# Andromeda-UIXO.net
KiCad netlist of a schematic drawn in Altium Designer
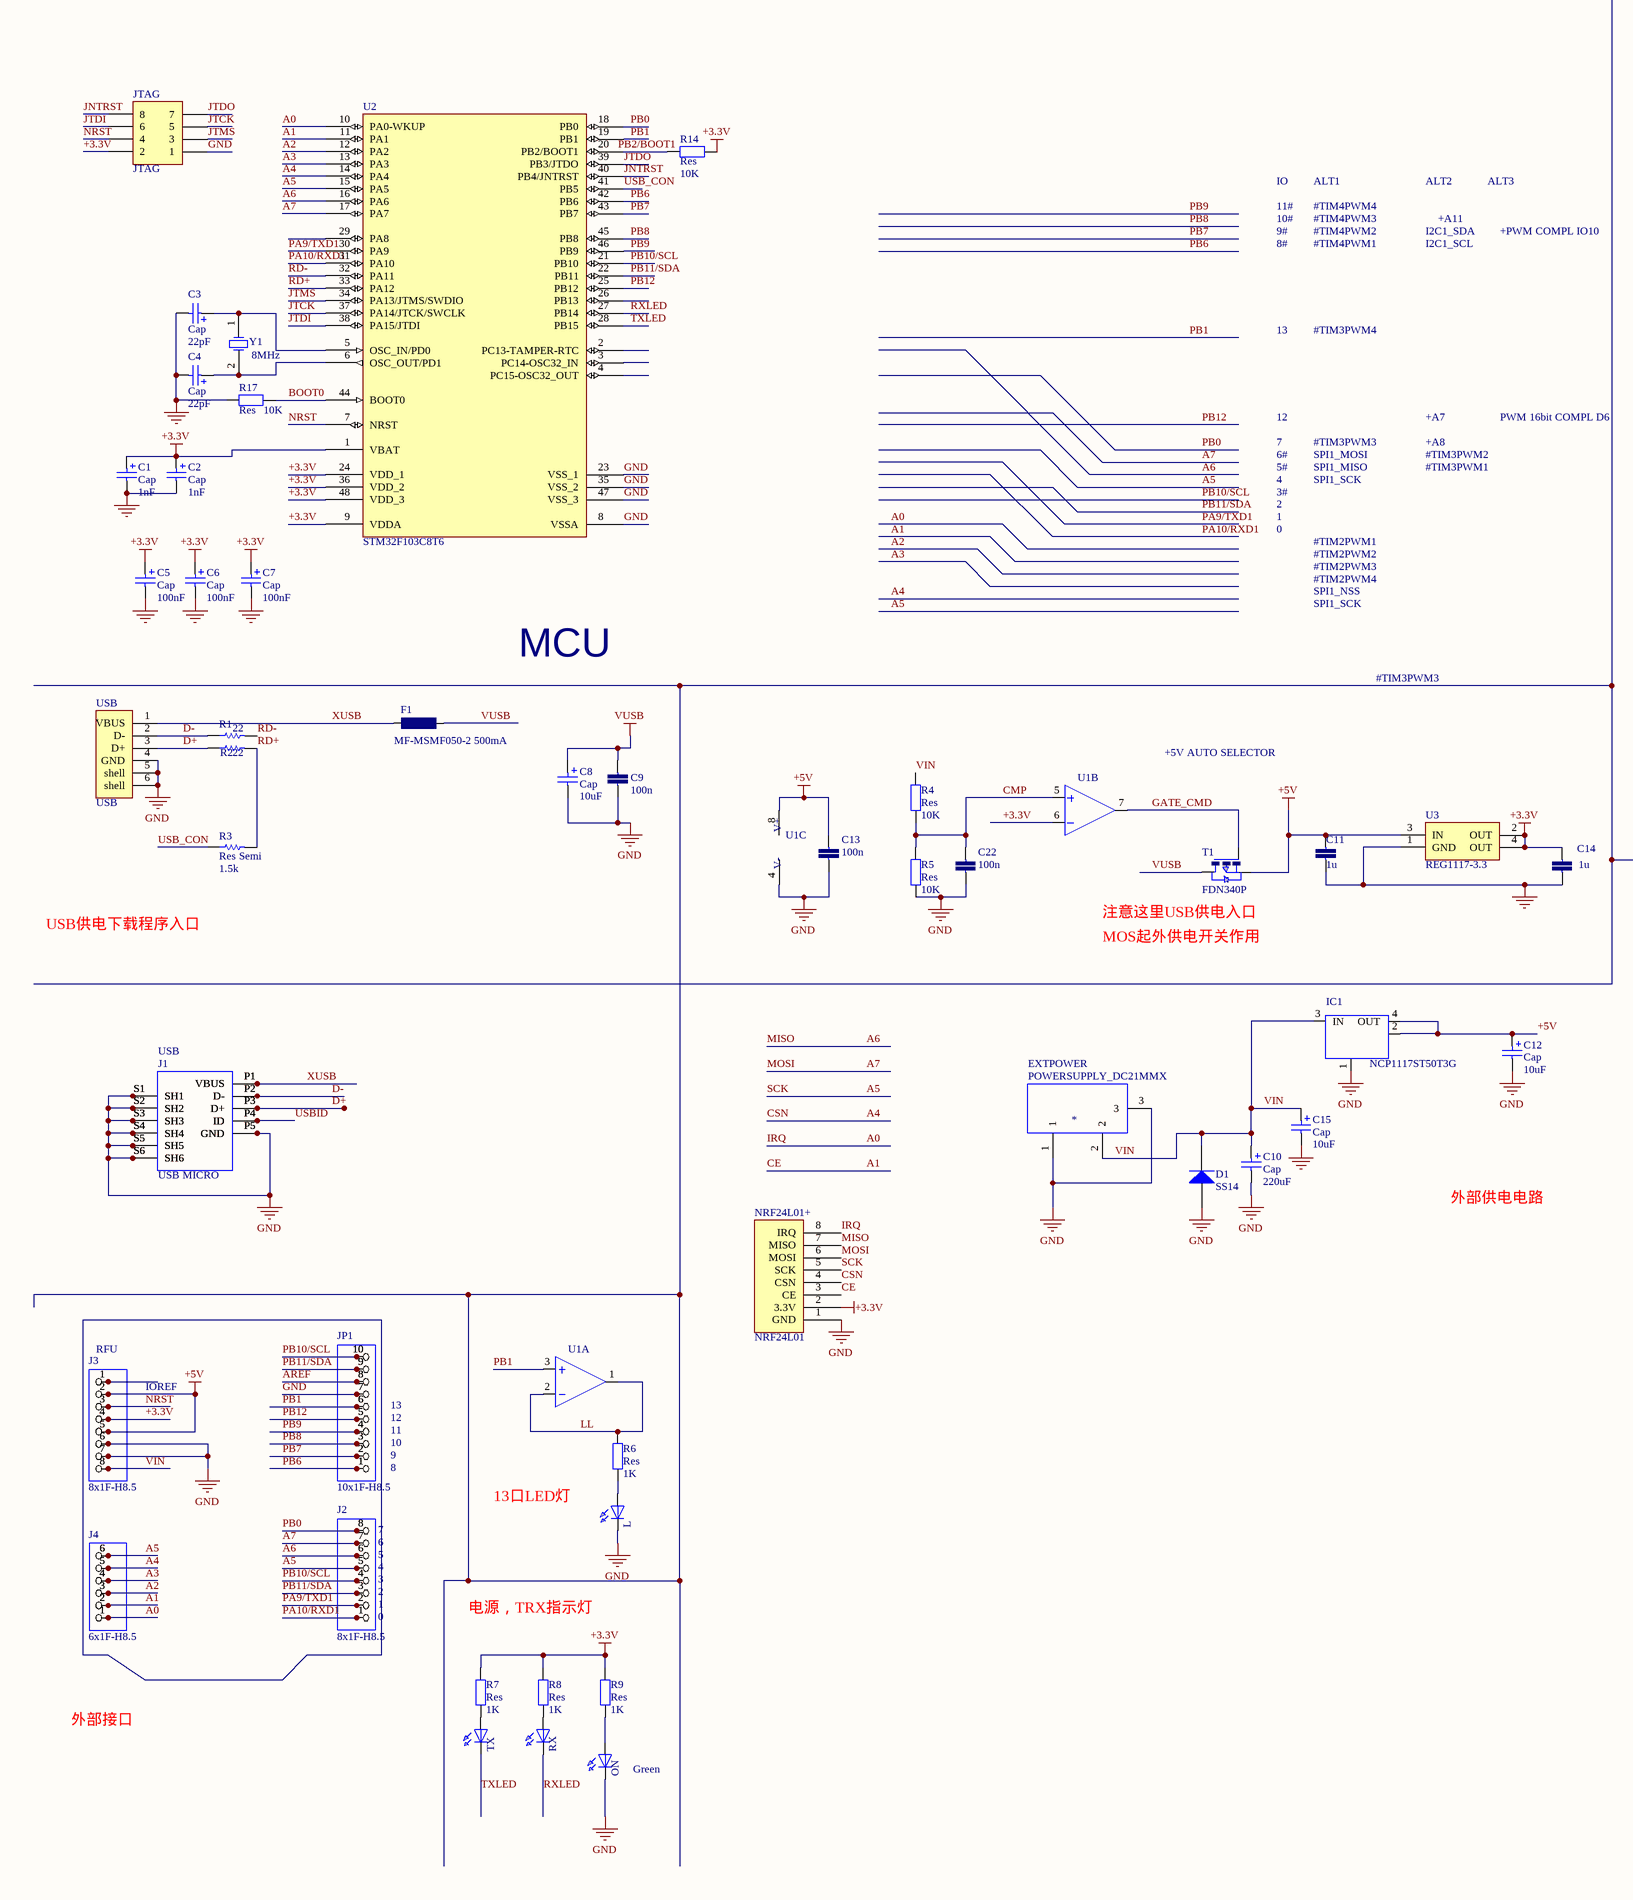
[diagram p0: Andromeda-UIXO.SchDoc, left]

(export (version "E")
  (design (tool "Eeschema 10.0.6"))
  (components
    (comp (ref "C1")
      (value "Cap")
      (footprint "RES0805(2012M)")
      (fields (field (name "ALTIUM_VALUE") "1nF"))
      (libsource (lib "*") (part "Cap"))
    )
    (comp (ref "C2")
      (value "Cap")
      (footprint "RES0805(2012M)")
      (fields (field (name "ALTIUM_VALUE") "1nF"))
      (libsource (lib "*") (part "Cap"))
    )
    (comp (ref "C3")
      (value "Cap")
      (footprint "RES0805(2012M)")
      (fields (field (name "ALTIUM_VALUE") "22pF"))
      (libsource (lib "*") (part "Cap"))
    )
    (comp (ref "C4")
      (value "Cap")
      (footprint "RES0805(2012M)")
      (fields (field (name "ALTIUM_VALUE") "22pF"))
      (libsource (lib "*") (part "Cap"))
    )
    (comp (ref "C5")
      (value "Cap")
      (footprint "RES0805(2012M)")
      (fields (field (name "ALTIUM_VALUE") "100nF"))
      (libsource (lib "*") (part "Cap"))
    )
    (comp (ref "C6")
      (value "Cap")
      (footprint "RES0805(2012M)")
      (fields (field (name "ALTIUM_VALUE") "100nF"))
      (libsource (lib "*") (part "Cap"))
    )
    (comp (ref "C7")
      (value "Cap")
      (footprint "RES0805(2012M)")
      (fields (field (name "ALTIUM_VALUE") "100nF"))
      (libsource (lib "*") (part "Cap"))
    )
    (comp (ref "C8")
      (value "Cap")
      (footprint "RES0805(2012M)")
      (fields (field (name "ALTIUM_VALUE") "10uF"))
      (libsource (lib "*") (part "Cap"))
    )
    (comp (ref "C9")
      (value "100n")
      (footprint "RES0805(2012M)")
      (libsource (lib "SmartPrj") (part "C-EUC0603"))
    )
    (comp (ref "C10")
      (value "Cap")
      (footprint "CAP_SMD")
      (fields (field (name "ALTIUM_VALUE") "220uF"))
      (libsource (lib "*") (part "Cap"))
    )
    (comp (ref "C11")
      (value "1u")
      (footprint "RES0805(2012M)")
      (libsource (lib "SmartPrj") (part "C-EUC0603"))
    )
    (comp (ref "C12")
      (value "Cap")
      (footprint "RES0805(2012M)")
      (fields (field (name "ALTIUM_VALUE") "10uF"))
      (libsource (lib "*") (part "Cap"))
    )
    (comp (ref "C13") (value "100n") (footprint "RES0805(2012M)") (libsource (lib "") (part "C-EUC0603_1")))
    (comp (ref "C14") (value "1u") (footprint "RES0805(2012M)") (libsource (lib "") (part "C-EUC0603_2")))
    (comp (ref "C15")
      (value "Cap")
      (footprint "RES0805(2012M)")
      (fields (field (name "ALTIUM_VALUE") "10uF"))
      (libsource (lib "*") (part "Cap"))
    )
    (comp (ref "C22")
      (value "100n")
      (footprint "RES0805(2012M)")
      (libsource (lib "SmartPrj") (part "C-EUC0603"))
    )
    (comp (ref "D1") (value "SS14") (footprint "DIODE_SMA") (libsource (lib "*") (part "DIODE_SWITCH")))
    (comp (ref "EXTPOWER")
      (value "*")
      (footprint "POWERSUPPLY_DC-21MM")
      (libsource (lib "SmartPrj") (part "POWERSUPPLY_DC21MMX"))
    )
    (comp (ref "F1")
      (value "MF-MSMF050-2 500mA")
      (footprint "L1812")
      (libsource (lib "rcl") (part "L-EUL1812"))
    )
    (comp (ref "IC1")
      (value "NCP1117ST50T3G")
      (footprint "SOT223")
      (libsource (lib "linear") (part "MC33269ST-3.3T3"))
    )
    (comp (ref "J1")
      (value "USB MICRO")
      (footprint "CON2_USB_MICRO_B_AT")
      (libsource (lib "SmartPrj") (part "MYCON2_USB-MINI-B"))
    )
    (comp (ref "J2") (value "8x1F-H8.5") (footprint "1X08") (libsource (lib "SmartPrj") (part "PINHD-1X8")))
    (comp (ref "J3") (value "8x1F-H8.5") (footprint "1X08") (libsource (lib "SmartPrj") (part "PINHD-1X8")))
    (comp (ref "J4") (value "6x1F-H8.5") (footprint "1X06") (libsource (lib "SmartPrj") (part "PINHD-1X6")))
    (comp (ref "JP1")
      (value "10x1F-H8.5")
      (footprint "1X10")
      (libsource (lib "SmartPrj") (part "PINHD-1X10"))
    )
    (comp (ref "JTAG")
      (value "JTAG")
      (footprint "HDR2X4")
      (description "Header, 4-Pin, Dual row")
      (fields (field (name "PUBLISHER") "Altium Limited"))
      (libsource (lib "*") (part "Header 4X2"))
    )
    (comp (ref "L")
      (value "Yellow")
      (footprint "CHIPLED_0805")
      (libsource (lib "led") (part "LEDCHIPLED_0805"))
    )
    (comp (ref "NRF24L01+")
      (value "NRF24L01")
      (footprint "NRF24L01")
      (description "NRF24L01+")
      (libsource (lib "NRF24L01") (part "NRF24L01"))
    )
    (comp (ref "ON")
      (value "Green")
      (footprint "CHIPLED_0805")
      (libsource (lib "led") (part "LEDCHIPLED_0805"))
    )
    (comp (ref "R1")
      (value "22")
      (footprint "RES0805(2012M)")
      (description "Semiconductor Resistor")
      (fields (field (name "Comment") "Res Semi") (field (name "PUBLISHER") "Altium Limited"))
      (libsource (lib "Miscellaneous Devices") (part "Res Semi"))
    )
    (comp (ref "R2")
      (value "22")
      (footprint "RES0805(2012M)")
      (description "Semiconductor Resistor")
      (fields (field (name "Comment") "Res Semi") (field (name "PUBLISHER") "Altium Limited"))
      (libsource (lib "Miscellaneous Devices") (part "Res Semi"))
    )
    (comp (ref "R3")
      (value "Res Semi")
      (footprint "RES0805(2012M)")
      (description "Semiconductor Resistor")
      (fields (field (name "ALTIUM_VALUE") "1.5k") (field (name "PUBLISHER") "Altium Limited"))
      (libsource (lib "Miscellaneous Devices") (part "Res Semi"))
    )
    (comp (ref "R4")
      (value "Res")
      (footprint "RES0805(2012M)")
      (description "Resistor")
      (fields (field (name "ALTIUM_VALUE") "10K"))
      (libsource (lib "") (part "Res_1"))
    )
    (comp (ref "R5")
      (value "Res")
      (footprint "RES0805(2012M)")
      (description "Resistor")
      (fields (field (name "ALTIUM_VALUE") "10K"))
      (libsource (lib "") (part "Res_1"))
    )
    (comp (ref "R6")
      (value "Res")
      (footprint "RES0805(2012M)")
      (description "Resistor")
      (fields (field (name "ALTIUM_VALUE") "1K"))
      (libsource (lib "") (part "Res_1"))
    )
    (comp (ref "R7")
      (value "Res")
      (footprint "RES0805(2012M)")
      (description "Resistor")
      (fields (field (name "ALTIUM_VALUE") "1K"))
      (libsource (lib "") (part "Res_1"))
    )
    (comp (ref "R8")
      (value "Res")
      (footprint "RES0805(2012M)")
      (description "Resistor")
      (fields (field (name "ALTIUM_VALUE") "1K"))
      (libsource (lib "") (part "Res_1"))
    )
    (comp (ref "R9")
      (value "Res")
      (footprint "RES0805(2012M)")
      (description "Resistor")
      (fields (field (name "ALTIUM_VALUE") "1K"))
      (libsource (lib "") (part "Res_1"))
    )
    (comp (ref "R14")
      (value "Res")
      (footprint "RES0805(2012M)")
      (description "Resistor")
      (fields (field (name "ALTIUM_VALUE") "10K"))
      (libsource (lib "*") (part "Res"))
    )
    (comp (ref "R17")
      (value "Res")
      (footprint "RES0805(2012M)")
      (description "Resistor")
      (fields (field (name "ALTIUM_VALUE") "10K"))
      (libsource (lib "*") (part "Res"))
    )
    (comp (ref "RX")
      (value "Yellow")
      (footprint "CHIPLED_0805")
      (libsource (lib "led") (part "LEDCHIPLED_0805"))
    )
    (comp (ref "T1") (value "FDN340P") (footprint "SOT-23") (libsource (lib "zetex") (part "PMOSSOT23")))
    (comp (ref "TX")
      (value "Yellow")
      (footprint "CHIPLED_0805")
      (libsource (lib "led") (part "LEDCHIPLED_0805"))
    )
    (comp (ref "U1")
      (value "LMV358IDGKR")
      (footprint "SO-8 LM358")
      (libsource (lib "Andromeda-UIXO") (part "LMV358MMX"))
    )
    (comp (ref "U2")
      (value "STM32F103C8T6")
      (footprint "LQFP48_M")
      (description "STM32 ARM-based 32-bit MCU with 64 Kbytes Flash, 48-pin LQFP, Industrial Temperature")
      (fields (field (name "PUBLISHER") "Altium Limited"))
      (libsource (lib "*") (part "STM32F103C8T6"))
    )
    (comp (ref "U3")
      (value "REG1117-3.3")
      (footprint "SOT223")
      (description "800mA and 1A Low Dropout Positive Regulator 2.85V, 3.3V, 5V, and Adjustable")
      (fields (field (name "PUBLISHER") "Altium Limited"))
      (libsource (lib "*") (part "REG1117-3.3"))
    )
    (comp (ref "USB") (value "USB") (footprint "USB/SM2.5-4H4A") (libsource (lib "*") (part "USB")))
    (comp (ref "Y1")
      (value "8MHz")
      (footprint "XTAL_0.4")
      (description "Crystal Oscillator")
      (fields (field (name "PUBLISHER") "Altium Limited"))
      (libsource (lib "*") (part "XTAL"))
    )
  )
  (nets
    (net (code "1") (name "+3.3V") (class "Default")
      (node (ref "C1") (pin "1") (pinfunction "1_1") (pintype "passive"))
      (node (ref "C14") (pin "2") (pinfunction "2_2") (pintype "passive"))
      (node (ref "C2") (pin "1") (pinfunction "1_1") (pintype "passive"))
      (node (ref "C5") (pin "1") (pinfunction "1_1") (pintype "passive"))
      (node (ref "C6") (pin "1") (pinfunction "1_1") (pintype "passive"))
      (node (ref "C7") (pin "1") (pinfunction "1_1") (pintype "passive"))
      (node (ref "J3") (pin "4") (pinfunction "4_4") (pintype "passive"))
      (node (ref "JTAG") (pin "2") (pinfunction "2_2") (pintype "passive"))
      (node (ref "NRF24L01+") (pin "2") (pinfunction "3.3V_2") (pintype "passive"))
      (node (ref "R14") (pin "1") (pinfunction "1_1") (pintype "passive"))
      (node (ref "R7") (pin "1") (pinfunction "1_1") (pintype "passive"))
      (node (ref "R8") (pin "1") (pinfunction "1_1") (pintype "passive"))
      (node (ref "R9") (pin "1") (pinfunction "1_1") (pintype "passive"))
      (node (ref "U1") (pin "6") (pinfunction "-IN_6") (pintype "passive"))
      (node (ref "U2") (pin "1") (pinfunction "VBAT_1") (pintype "power_in"))
      (node (ref "U2") (pin "24") (pinfunction "VDD_1_24") (pintype "power_in"))
      (node (ref "U2") (pin "36") (pinfunction "VDD_2_36") (pintype "power_in"))
      (node (ref "U2") (pin "48") (pinfunction "VDD_3_48") (pintype "power_in"))
      (node (ref "U2") (pin "9") (pinfunction "VDDA_9") (pintype "power_in"))
      (node (ref "U3") (pin "2") (pinfunction "OUT_2") (pintype "power_in"))
      (node (ref "U3") (pin "4") (pinfunction "OUT_4") (pintype "power_in"))
    )
    (net (code "2") (name "+5V") (class "Default")
      (node (ref "C11") (pin "2") (pinfunction "2_2") (pintype "passive"))
      (node (ref "C12") (pin "1") (pinfunction "1_1") (pintype "passive"))
      (node (ref "C13") (pin "1") (pinfunction "1_1") (pintype "passive"))
      (node (ref "IC1") (pin "2") (pinfunction "OUT@1_2") (pintype "passive"))
      (node (ref "IC1") (pin "4") (pinfunction "OUT_4") (pintype "passive"))
      (node (ref "J3") (pin "2") (pinfunction "2_2") (pintype "passive"))
      (node (ref "J3") (pin "5") (pinfunction "5_5") (pintype "passive"))
      (node (ref "T1") (pin "2") (pinfunction "S_2") (pintype "passive"))
      (node (ref "U1") (pin "8") (pinfunction "V+_8") (pintype "passive"))
      (node (ref "U3") (pin "3") (pinfunction "IN_3") (pintype "power_in"))
    )
    (net (code "3") (name "/A0") (class "Default")
      (node (ref "J4") (pin "1") (pinfunction "1_1") (pintype "passive"))
      (node (ref "NRF24L01+") (pin "8") (pinfunction "IRQ_8") (pintype "passive"))
      (node (ref "U2") (pin "10") (pinfunction "PA0-WKUP_10") (pintype "bidirectional"))
    )
    (net (code "4") (name "/A1") (class "Default")
      (node (ref "J4") (pin "2") (pinfunction "2_2") (pintype "passive"))
      (node (ref "NRF24L01+") (pin "3") (pinfunction "CE_3") (pintype "passive"))
      (node (ref "U2") (pin "11") (pinfunction "PA1_11") (pintype "bidirectional"))
    )
    (net (code "5") (name "/A2") (class "Default")
      (node (ref "J4") (pin "3") (pinfunction "3_3") (pintype "passive"))
      (node (ref "U2") (pin "12") (pinfunction "PA2_12") (pintype "bidirectional"))
    )
    (net (code "6") (name "/A3") (class "Default")
      (node (ref "J4") (pin "4") (pinfunction "4_4") (pintype "passive"))
      (node (ref "U2") (pin "13") (pinfunction "PA3_13") (pintype "bidirectional"))
    )
    (net (code "7") (name "/A4") (class "Default")
      (node (ref "J4") (pin "5") (pinfunction "5_5") (pintype "passive"))
      (node (ref "NRF24L01+") (pin "4") (pinfunction "CSN_4") (pintype "passive"))
      (node (ref "U2") (pin "14") (pinfunction "PA4_14") (pintype "bidirectional"))
    )
    (net (code "8") (name "/A5") (class "Default")
      (node (ref "J2") (pin "5") (pinfunction "5_5") (pintype "passive"))
      (node (ref "J4") (pin "6") (pinfunction "6_6") (pintype "passive"))
      (node (ref "NRF24L01+") (pin "5") (pinfunction "SCK_5") (pintype "passive"))
      (node (ref "U2") (pin "15") (pinfunction "PA5_15") (pintype "bidirectional"))
    )
    (net (code "9") (name "/A6") (class "Default")
      (node (ref "J2") (pin "6") (pinfunction "6_6") (pintype "passive"))
      (node (ref "NRF24L01+") (pin "7") (pinfunction "MISO_7") (pintype "passive"))
      (node (ref "U2") (pin "16") (pinfunction "PA6_16") (pintype "bidirectional"))
    )
    (net (code "10") (name "/A7") (class "Default")
      (node (ref "J2") (pin "7") (pinfunction "7_7") (pintype "passive"))
      (node (ref "NRF24L01+") (pin "6") (pinfunction "MOSI_6") (pintype "passive"))
      (node (ref "U2") (pin "17") (pinfunction "PA7_17") (pintype "bidirectional"))
    )
    (net (code "11") (name "/AREF") (class "Default")
      (node (ref "JP1") (pin "8") (pinfunction "8_8") (pintype "passive"))
    )
    (net (code "12") (name "/BOOT0") (class "Default")
      (node (ref "R17") (pin "1") (pinfunction "1_1") (pintype "passive"))
      (node (ref "U2") (pin "44") (pinfunction "BOOT0_44") (pintype "input"))
    )
    (net (code "13") (name "/CMP") (class "Default")
      (node (ref "C22") (pin "2") (pinfunction "2_2") (pintype "passive"))
      (node (ref "R4") (pin "2") (pinfunction "2_2") (pintype "passive"))
      (node (ref "R5") (pin "1") (pinfunction "1_1") (pintype "passive"))
      (node (ref "U1") (pin "5") (pinfunction "+IN_5") (pintype "passive"))
    )
    (net (code "14") (name "/D+") (class "Default")
      (node (ref "J1") (pin "P3") (pinfunction "D+_P3") (pintype "passive"))
      (node (ref "R2") (pin "1") (pinfunction "1_1") (pintype "passive"))
      (node (ref "USB") (pin "3") (pinfunction "D+_3") (pintype "passive"))
    )
    (net (code "15") (name "/D-") (class "Default")
      (node (ref "J1") (pin "P2") (pinfunction "D-_P2") (pintype "passive"))
      (node (ref "R1") (pin "1") (pinfunction "1_1") (pintype "passive"))
      (node (ref "USB") (pin "2") (pinfunction "D-_2") (pintype "passive"))
    )
    (net (code "16") (name "/GATE_CMD") (class "Default")
      (node (ref "T1") (pin "3") (pinfunction "G_3") (pintype "passive"))
      (node (ref "U1") (pin "7") (pinfunction "OUT_7") (pintype "passive"))
    )
    (net (code "17") (name "/JNTRST") (class "Default")
      (node (ref "JTAG") (pin "8") (pinfunction "8_8") (pintype "passive"))
      (node (ref "U2") (pin "40") (pinfunction "PB4/JNTRST_40") (pintype "bidirectional"))
    )
    (net (code "18") (name "/JTCK") (class "Default")
      (node (ref "JTAG") (pin "5") (pinfunction "5_5") (pintype "passive"))
      (node (ref "U2") (pin "37") (pinfunction "PA14/JTCK/SWCLK_37") (pintype "bidirectional"))
    )
    (net (code "19") (name "/JTDI") (class "Default")
      (node (ref "JTAG") (pin "6") (pinfunction "6_6") (pintype "passive"))
      (node (ref "U2") (pin "38") (pinfunction "PA15/JTDI_38") (pintype "bidirectional"))
    )
    (net (code "20") (name "/JTDO") (class "Default")
      (node (ref "JTAG") (pin "7") (pinfunction "7_7") (pintype "passive"))
      (node (ref "U2") (pin "39") (pinfunction "PB3/JTDO_39") (pintype "bidirectional"))
    )
    (net (code "21") (name "/JTMS") (class "Default")
      (node (ref "JTAG") (pin "3") (pinfunction "3_3") (pintype "passive"))
      (node (ref "U2") (pin "34") (pinfunction "PA13/JTMS/SWDIO_34") (pintype "bidirectional"))
    )
    (net (code "22") (name "/LL") (class "Default")
      (node (ref "R6") (pin "1") (pinfunction "1_1") (pintype "passive"))
      (node (ref "U1") (pin "1") (pinfunction "OUT_1") (pintype "passive"))
      (node (ref "U1") (pin "2") (pinfunction "-IN_2") (pintype "passive"))
    )
    (net (code "23") (name "/NRST") (class "Default")
      (node (ref "J3") (pin "3") (pinfunction "3_3") (pintype "passive"))
      (node (ref "JTAG") (pin "4") (pinfunction "4_4") (pintype "passive"))
      (node (ref "U2") (pin "7") (pinfunction "NRST_7") (pintype "bidirectional"))
    )
    (net (code "24") (name "/PA9{slash}TXD1") (class "Default")
      (node (ref "J2") (pin "2") (pinfunction "2_2") (pintype "passive"))
      (node (ref "U2") (pin "30") (pinfunction "PA9_30") (pintype "bidirectional"))
    )
    (net (code "25") (name "/PA10{slash}RXD1") (class "Default")
      (node (ref "J2") (pin "1") (pinfunction "1_1") (pintype "passive"))
      (node (ref "U2") (pin "31") (pinfunction "PA10_31") (pintype "bidirectional"))
    )
    (net (code "26") (name "/PB0") (class "Default")
      (node (ref "J2") (pin "8") (pinfunction "8_8") (pintype "passive"))
      (node (ref "U2") (pin "18") (pinfunction "PB0_18") (pintype "bidirectional"))
    )
    (net (code "27") (name "/PB1") (class "Default")
      (node (ref "JP1") (pin "6") (pinfunction "6_6") (pintype "passive"))
      (node (ref "U1") (pin "3") (pinfunction "+IN_3") (pintype "passive"))
      (node (ref "U2") (pin "19") (pinfunction "PB1_19") (pintype "bidirectional"))
    )
    (net (code "29") (name "/PB6") (class "Default")
      (node (ref "JP1") (pin "1") (pinfunction "1_1") (pintype "passive"))
      (node (ref "U2") (pin "42") (pinfunction "PB6_42") (pintype "bidirectional"))
    )
    (net (code "30") (name "/PB7") (class "Default")
      (node (ref "JP1") (pin "2") (pinfunction "2_2") (pintype "passive"))
      (node (ref "U2") (pin "43") (pinfunction "PB7_43") (pintype "bidirectional"))
    )
    (net (code "31") (name "/PB8") (class "Default")
      (node (ref "JP1") (pin "3") (pinfunction "3_3") (pintype "passive"))
      (node (ref "U2") (pin "45") (pinfunction "PB8_45") (pintype "bidirectional"))
    )
    (net (code "32") (name "/PB9") (class "Default")
      (node (ref "JP1") (pin "4") (pinfunction "4_4") (pintype "passive"))
      (node (ref "U2") (pin "46") (pinfunction "PB9_46") (pintype "bidirectional"))
    )
    (net (code "33") (name "/PB10{slash}SCL") (class "Default")
      (node (ref "J2") (pin "4") (pinfunction "4_4") (pintype "passive"))
      (node (ref "JP1") (pin "10") (pinfunction "10_10") (pintype "passive"))
      (node (ref "U2") (pin "21") (pinfunction "PB10_21") (pintype "bidirectional"))
    )
    (net (code "34") (name "/PB11{slash}SDA") (class "Default")
      (node (ref "J2") (pin "3") (pinfunction "3_3") (pintype "passive"))
      (node (ref "JP1") (pin "9") (pinfunction "9_9") (pintype "passive"))
      (node (ref "U2") (pin "22") (pinfunction "PB11_22") (pintype "bidirectional"))
    )
    (net (code "35") (name "/PB12") (class "Default")
      (node (ref "JP1") (pin "5") (pinfunction "5_5") (pintype "passive"))
      (node (ref "U2") (pin "25") (pinfunction "PB12_25") (pintype "bidirectional"))
    )
    (net (code "36") (name "/RD+") (class "Default")
      (node (ref "R2") (pin "2") (pinfunction "2_2") (pintype "passive"))
      (node (ref "R3") (pin "2") (pinfunction "2_2") (pintype "passive"))
      (node (ref "U2") (pin "33") (pinfunction "PA12_33") (pintype "bidirectional"))
    )
    (net (code "37") (name "/RD-") (class "Default")
      (node (ref "R1") (pin "2") (pinfunction "2_2") (pintype "passive"))
      (node (ref "U2") (pin "32") (pinfunction "PA11_32") (pintype "bidirectional"))
    )
    (net (code "38") (name "/RXLED") (class "Default")
      (node (ref "RX") (pin "C") (pinfunction "C_C") (pintype "passive"))
      (node (ref "U2") (pin "27") (pinfunction "PB14_27") (pintype "bidirectional"))
    )
    (net (code "39") (name "/TXLED") (class "Default")
      (node (ref "TX") (pin "C") (pinfunction "C_C") (pintype "passive"))
      (node (ref "U2") (pin "28") (pinfunction "PB15_28") (pintype "bidirectional"))
    )
    (net (code "40") (name "/USBID") (class "Default")
      (node (ref "J1") (pin "P4") (pinfunction "ID_P4") (pintype "passive"))
    )
    (net (code "41") (name "/USB_CON") (class "Default")
      (node (ref "R3") (pin "1") (pinfunction "1_1") (pintype "passive"))
      (node (ref "U2") (pin "41") (pinfunction "PB5_41") (pintype "bidirectional"))
    )
    (net (code "42") (name "/VIN") (class "Default")
      (node (ref "C10") (pin "1") (pinfunction "1_1") (pintype "passive"))
      (node (ref "C15") (pin "1") (pinfunction "1_1") (pintype "passive"))
      (node (ref "D1") (pin "2") (pinfunction "K_2") (pintype "passive"))
      (node (ref "EXTPOWER") (pin "2") (pinfunction "2_2") (pintype "passive"))
      (node (ref "IC1") (pin "3") (pinfunction "IN_3") (pintype "passive"))
      (node (ref "J3") (pin "8") (pinfunction "8_8") (pintype "passive"))
      (node (ref "R4") (pin "1") (pinfunction "1_1") (pintype "passive"))
    )
    (net (code "43") (name "/XUSB") (class "Default")
      (node (ref "F1") (pin "2") (pinfunction "2_2") (pintype "passive"))
      (node (ref "J1") (pin "P1") (pinfunction "VBUS_P1") (pintype "passive"))
      (node (ref "USB") (pin "1") (pinfunction "VBUS_1") (pintype "passive"))
    )
    (net (code "44") (name "GND") (class "Default")
      (node (ref "C1") (pin "2") (pinfunction "2_2") (pintype "passive"))
      (node (ref "C10") (pin "2") (pinfunction "2_2") (pintype "passive"))
      (node (ref "C11") (pin "1") (pinfunction "1_1") (pintype "passive"))
      (node (ref "C12") (pin "2") (pinfunction "2_2") (pintype "passive"))
      (node (ref "C13") (pin "2") (pinfunction "2_2") (pintype "passive"))
      (node (ref "C14") (pin "1") (pinfunction "1_1") (pintype "passive"))
      (node (ref "C15") (pin "2") (pinfunction "2_2") (pintype "passive"))
      (node (ref "C2") (pin "2") (pinfunction "2_2") (pintype "passive"))
      (node (ref "C22") (pin "1") (pinfunction "1_1") (pintype "passive"))
      (node (ref "C3") (pin "2") (pinfunction "2_2") (pintype "passive"))
      (node (ref "C4") (pin "2") (pinfunction "2_2") (pintype "passive"))
      (node (ref "C5") (pin "2") (pinfunction "2_2") (pintype "passive"))
      (node (ref "C6") (pin "2") (pinfunction "2_2") (pintype "passive"))
      (node (ref "C7") (pin "2") (pinfunction "2_2") (pintype "passive"))
      (node (ref "C8") (pin "2") (pinfunction "2_2") (pintype "passive"))
      (node (ref "C9") (pin "1") (pinfunction "1_1") (pintype "passive"))
      (node (ref "D1") (pin "1") (pinfunction "A_1") (pintype "passive"))
      (node (ref "EXTPOWER") (pin "1") (pinfunction "1_1") (pintype "passive"))
      (node (ref "EXTPOWER") (pin "3") (pinfunction "3_3") (pintype "passive"))
      (node (ref "IC1") (pin "1") (pinfunction "GND/ADJ_1") (pintype "passive"))
      (node (ref "J1") (pin "P5") (pinfunction "GND_P5") (pintype "passive"))
      (node (ref "J1") (pin "S1") (pinfunction "SH1_S1") (pintype "passive"))
      (node (ref "J1") (pin "S2") (pinfunction "SH2_S2") (pintype "passive"))
      (node (ref "J1") (pin "S3") (pinfunction "SH3_S3") (pintype "passive"))
      (node (ref "J1") (pin "S4") (pinfunction "SH4_S4") (pintype "passive"))
      (node (ref "J1") (pin "S5") (pinfunction "SH5_S5") (pintype "passive"))
      (node (ref "J1") (pin "S6") (pinfunction "SH6_S6") (pintype "passive"))
      (node (ref "J3") (pin "6") (pinfunction "6_6") (pintype "passive"))
      (node (ref "J3") (pin "7") (pinfunction "7_7") (pintype "passive"))
      (node (ref "JP1") (pin "7") (pinfunction "7_7") (pintype "passive"))
      (node (ref "JTAG") (pin "1") (pinfunction "1_1") (pintype "passive"))
      (node (ref "L") (pin "C") (pinfunction "C_C") (pintype "passive"))
      (node (ref "NRF24L01+") (pin "1") (pinfunction "GND_1") (pintype "passive"))
      (node (ref "ON") (pin "C") (pinfunction "C_C") (pintype "passive"))
      (node (ref "R17") (pin "2") (pinfunction "2_2") (pintype "passive"))
      (node (ref "R5") (pin "2") (pinfunction "2_2") (pintype "passive"))
      (node (ref "U1") (pin "4") (pinfunction "V-_4") (pintype "passive"))
      (node (ref "U2") (pin "23") (pinfunction "VSS_1_23") (pintype "power_in"))
      (node (ref "U2") (pin "35") (pinfunction "VSS_2_35") (pintype "power_in"))
      (node (ref "U2") (pin "47") (pinfunction "VSS_3_47") (pintype "power_in"))
      (node (ref "U2") (pin "8") (pinfunction "VSSA_8") (pintype "power_in"))
      (node (ref "U3") (pin "1") (pinfunction "GND_1") (pintype "power_in"))
      (node (ref "USB") (pin "4") (pinfunction "GND_4") (pintype "passive"))
      (node (ref "USB") (pin "5") (pinfunction "shell_5") (pintype "passive"))
      (node (ref "USB") (pin "6") (pinfunction "shell_6") (pintype "passive"))
    )
    (net (code "45") (name "Net-(J3-Pad1)") (class "Default")
      (node (ref "J3") (pin "1") (pinfunction "1_1") (pintype "passive"))
    )
    (net (code "46") (name "Net-(L-PadA)") (class "Default")
      (node (ref "L") (pin "A") (pinfunction "A_A") (pintype "passive"))
      (node (ref "R6") (pin "2") (pinfunction "2_2") (pintype "passive"))
    )
    (net (code "47") (name "Net-(ON-PadA)") (class "Default")
      (node (ref "ON") (pin "A") (pinfunction "A_A") (pintype "passive"))
      (node (ref "R9") (pin "2") (pinfunction "2_2") (pintype "passive"))
    )
    (net (code "48") (name "Net-(R7-Pad2)") (class "Default")
      (node (ref "R7") (pin "2") (pinfunction "2_2") (pintype "passive"))
      (node (ref "TX") (pin "A") (pinfunction "A_A") (pintype "passive"))
    )
    (net (code "49") (name "Net-(R8-Pad2)") (class "Default")
      (node (ref "R8") (pin "2") (pinfunction "2_2") (pintype "passive"))
      (node (ref "RX") (pin "A") (pinfunction "A_A") (pintype "passive"))
    )
    (net (code "50") (name "Net-(U2-OSC_IN{slash}PD0)") (class "Default")
      (node (ref "C3") (pin "1") (pinfunction "1_1") (pintype "passive"))
      (node (ref "U2") (pin "5") (pinfunction "OSC_IN/PD0_5") (pintype "input"))
      (node (ref "Y1") (pin "1") (pinfunction "OSC1_1") (pintype "passive"))
    )
    (net (code "51") (name "Net-(U2-OSC_OUT{slash}PD1)") (class "Default")
      (node (ref "C4") (pin "1") (pinfunction "1_1") (pintype "passive"))
      (node (ref "U2") (pin "6") (pinfunction "OSC_OUT/PD1_6") (pintype "output"))
      (node (ref "Y1") (pin "2") (pinfunction "OSC2_2") (pintype "passive"))
    )
    (net (code "52") (name "Net-(U2-PB2{slash}BOOT1)") (class "Default")
      (node (ref "R14") (pin "2") (pinfunction "2_2") (pintype "passive"))
      (node (ref "U2") (pin "20") (pinfunction "PB2/BOOT1_20") (pintype "bidirectional"))
    )
    (net (code "53") (name "VUSB") (class "Default")
      (node (ref "C8") (pin "1") (pinfunction "1_1") (pintype "passive"))
      (node (ref "C9") (pin "2") (pinfunction "2_2") (pintype "passive"))
      (node (ref "F1") (pin "1") (pinfunction "1_1") (pintype "passive"))
      (node (ref "T1") (pin "1") (pinfunction "D_1") (pintype "passive"))
    )
    (net (code "54") (name "unconnected-(U2-PA8-Pad29)") (class "Default")
      (node (ref "U2") (pin "29") (pinfunction "PA8_29") (pintype "bidirectional"))
    )
    (net (code "55") (name "unconnected-(U2-PB13-Pad26)") (class "Default")
      (node (ref "U2") (pin "26") (pinfunction "PB13_26") (pintype "bidirectional"))
    )
    (net (code "56") (name "unconnected-(U2-PC13-TAMPER-RTC-Pad2)") (class "Default")
      (node (ref "U2") (pin "2") (pinfunction "PC13-TAMPER-RTC_2") (pintype "bidirectional"))
    )
    (net (code "57") (name "unconnected-(U2-PC14-OSC32_IN-Pad3)") (class "Default")
      (node (ref "U2") (pin "3") (pinfunction "PC14-OSC32_IN_3") (pintype "bidirectional"))
    )
    (net (code "58") (name "unconnected-(U2-PC15-OSC32_OUT-Pad4)") (class "Default")
      (node (ref "U2") (pin "4") (pinfunction "PC15-OSC32_OUT_4") (pintype "bidirectional"))
    )
  )
)
